# Sheet1.net
KiCad netlist of a schematic drawn in Altium Designer
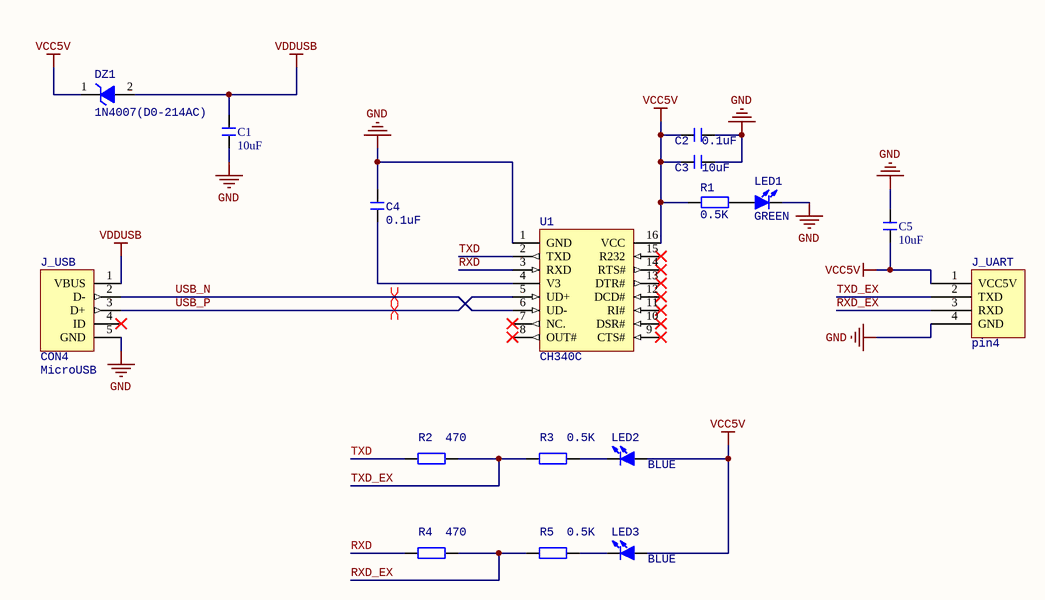
[diagram p0: Sheet1.SchDoc]

(export (version "E")
  (design (tool "Eeschema 10.0.6"))
  (components
    (comp (ref "C1")
      (value "10uF")
      (footprint "C 0603_M")
      (description "无极性贴片电容")
      (fields (field (name "版权归属") "源创客"))
      (libsource (lib "Schlib1") (part "C"))
    )
    (comp (ref "C2")
      (value "0.1uF")
      (footprint "C 0402_M")
      (description "无极性贴片电容")
      (fields (field (name "版权归属") "源创客"))
      (libsource (lib "Schlib2") (part "C"))
    )
    (comp (ref "C3")
      (value "10uF")
      (footprint "C 0603_M")
      (description "无极性贴片电容")
      (fields (field (name "版权归属") "源创客"))
      (libsource (lib "Schlib2") (part "C"))
    )
    (comp (ref "C4")
      (value "0.1uF")
      (footprint "C 0402_M")
      (description "无极性贴片电容")
      (fields (field (name "版权归属") "源创客"))
      (libsource (lib "Schlib2") (part "C"))
    )
    (comp (ref "C5")
      (value "10uF")
      (footprint "C 0603_M")
      (description "无极性贴片电容")
      (fields (field (name "版权归属") "源创客"))
      (libsource (lib "Schlib1") (part "C"))
    )
    (comp (ref "DZ1")
      (value "1N4007(D0-214AC)")
      (footprint "D SMA(DO-214AC)")
      (description "稳压二极管")
      (fields (field (name "版权归属") "源创客"))
      (libsource (lib "Schlib1") (part "DZ"))
    )
    (comp (ref "J_UART") (value "pin4") (footprint "HDR2.54-LI-4P") (libsource (lib "Schlib1") (part "pin4")))
    (comp (ref "J_USB")
      (value "CON4")
      (footprint "MicroUsb_C404969")
      (libsource (lib "Schlib1") (part "MicroUSB_5P"))
    )
    (comp (ref "LED1")
      (value "GREEN")
      (footprint "D 0402")
      (description "贴片LED")
      (fields (field (name "版权归属") "源创客"))
      (libsource (lib "Schlib2") (part "LED-SMD"))
    )
    (comp (ref "LED2")
      (value "BLUE")
      (footprint "D 0402")
      (description "贴片LED")
      (fields (field (name "版权归属") "源创客"))
      (libsource (lib "Schlib2") (part "LED-SMD"))
    )
    (comp (ref "LED3")
      (value "BLUE")
      (footprint "D 0402")
      (description "贴片LED")
      (fields (field (name "版权归属") "源创客"))
      (libsource (lib "Schlib2") (part "LED-SMD"))
    )
    (comp (ref "R1")
      (value "0.5K")
      (footprint "R 0402R")
      (description "贴片电阻")
      (libsource (lib "Schlib2") (part "R"))
    )
    (comp (ref "R2")
      (value "470")
      (footprint "R 0402R")
      (description "贴片电阻")
      (libsource (lib "Schlib2") (part "R"))
    )
    (comp (ref "R3")
      (value "0.5K")
      (footprint "R 0402R")
      (description "贴片电阻")
      (libsource (lib "Schlib2") (part "R"))
    )
    (comp (ref "R4")
      (value "470")
      (footprint "R 0402R")
      (description "贴片电阻")
      (libsource (lib "Schlib2") (part "R"))
    )
    (comp (ref "R5")
      (value "0.5K")
      (footprint "R 0402R")
      (description "贴片电阻")
      (libsource (lib "Schlib2") (part "R"))
    )
    (comp (ref "U1")
      (value "CH340C")
      (footprint "SOP-16_150mil")
      (description "CH340 是一个 USB 总线的转接芯片，实现 USB 转串口或者 USB 转打印口。")
      (libsource (lib "Schlib1") (part "CH340C"))
    )
  )
  (nets
    (net (code "1") (name "/RXD") (class "Default")
      (node (ref "R4") (pin "1") (pinfunction "1_1") (pintype "passive"))
      (node (ref "U1") (pin "3") (pinfunction "RXD_3") (pintype "input"))
    )
    (net (code "2") (name "/RXD_EX") (class "Default")
      (node (ref "J_UART") (pin "3") (pinfunction "RXD_3") (pintype "passive"))
      (node (ref "R4") (pin "2") (pinfunction "2_2") (pintype "passive"))
      (node (ref "R5") (pin "1") (pinfunction "1_1") (pintype "passive"))
    )
    (net (code "3") (name "/TXD") (class "Default")
      (node (ref "R2") (pin "1") (pinfunction "1_1") (pintype "passive"))
      (node (ref "U1") (pin "2") (pinfunction "TXD_2") (pintype "output"))
    )
    (net (code "4") (name "/TXD_EX") (class "Default")
      (node (ref "J_UART") (pin "2") (pinfunction "TXD_2") (pintype "passive"))
      (node (ref "R2") (pin "2") (pinfunction "2_2") (pintype "passive"))
      (node (ref "R3") (pin "1") (pinfunction "1_1") (pintype "passive"))
    )
    (net (code "5") (name "/USB_N") (class "Default")
      (node (ref "J_USB") (pin "2") (pinfunction "D-_2") (pintype "output"))
      (node (ref "U1") (pin "6") (pinfunction "UD-_6") (pintype "input"))
    )
    (net (code "6") (name "/USB_P") (class "Default")
      (node (ref "J_USB") (pin "3") (pinfunction "D+_3") (pintype "output"))
      (node (ref "U1") (pin "5") (pinfunction "UD+_5") (pintype "input"))
    )
    (net (code "7") (name "GND") (class "Default")
      (node (ref "C1") (pin "1") (pinfunction "1_1") (pintype "passive"))
      (node (ref "C2") (pin "2") (pinfunction "2_2") (pintype "passive"))
      (node (ref "C3") (pin "2") (pinfunction "2_2") (pintype "passive"))
      (node (ref "C4") (pin "2") (pinfunction "2_2") (pintype "passive"))
      (node (ref "C5") (pin "2") (pinfunction "2_2") (pintype "passive"))
      (node (ref "J_UART") (pin "4") (pinfunction "GND_4") (pintype "passive"))
      (node (ref "J_USB") (pin "5") (pinfunction "GND_5") (pintype "power_in"))
      (node (ref "LED1") (pin "2") (pinfunction "K_2") (pintype "passive"))
      (node (ref "U1") (pin "1") (pinfunction "GND_1") (pintype "power_in"))
    )
    (net (code "8") (name "Net-(LED1-A)") (class "Default")
      (node (ref "LED1") (pin "1") (pinfunction "A_1") (pintype "passive"))
      (node (ref "R1") (pin "2") (pinfunction "2_2") (pintype "passive"))
    )
    (net (code "9") (name "Net-(LED2-K)") (class "Default")
      (node (ref "LED2") (pin "2") (pinfunction "K_2") (pintype "passive"))
      (node (ref "R3") (pin "2") (pinfunction "2_2") (pintype "passive"))
    )
    (net (code "10") (name "Net-(LED3-K)") (class "Default")
      (node (ref "LED3") (pin "2") (pinfunction "K_2") (pintype "passive"))
      (node (ref "R5") (pin "2") (pinfunction "2_2") (pintype "passive"))
    )
    (net (code "11") (name "Net-(U1-V3)") (class "Default")
      (node (ref "C4") (pin "1") (pinfunction "1_1") (pintype "passive"))
      (node (ref "U1") (pin "4") (pinfunction "V3_4") (pintype "power_in"))
    )
    (net (code "12") (name "VCC5V") (class "Default")
      (node (ref "C2") (pin "1") (pinfunction "1_1") (pintype "passive"))
      (node (ref "C3") (pin "1") (pinfunction "1_1") (pintype "passive"))
      (node (ref "C5") (pin "1") (pinfunction "1_1") (pintype "passive"))
      (node (ref "DZ1") (pin "1") (pinfunction "K_1") (pintype "passive"))
      (node (ref "J_UART") (pin "1") (pinfunction "VCC5V_1") (pintype "passive"))
      (node (ref "LED2") (pin "1") (pinfunction "A_1") (pintype "passive"))
      (node (ref "LED3") (pin "1") (pinfunction "A_1") (pintype "passive"))
      (node (ref "R1") (pin "1") (pinfunction "1_1") (pintype "passive"))
      (node (ref "U1") (pin "16") (pinfunction "VCC_16") (pintype "power_in"))
    )
    (net (code "13") (name "VDDUSB") (class "Default")
      (node (ref "C1") (pin "2") (pinfunction "2_2") (pintype "passive"))
      (node (ref "DZ1") (pin "2") (pinfunction "A_2") (pintype "passive"))
      (node (ref "J_USB") (pin "1") (pinfunction "VBUS_1") (pintype "power_in"))
    )
    (net (code "14") (name "unconnected-(J_USB-ID-Pad4)") (class "Default")
      (node (ref "J_USB") (pin "4") (pinfunction "ID_4") (pintype "passive+no_connect"))
    )
    (net (code "15") (name "unconnected-(U1-CTS#-Pad9)") (class "Default")
      (node (ref "U1") (pin "9") (pinfunction "CTS#_9") (pintype "input+no_connect"))
    )
    (net (code "16") (name "unconnected-(U1-DCD#-Pad12)") (class "Default")
      (node (ref "U1") (pin "12") (pinfunction "DCD#_12") (pintype "input+no_connect"))
    )
    (net (code "17") (name "unconnected-(U1-DSR#-Pad10)") (class "Default")
      (node (ref "U1") (pin "10") (pinfunction "DSR#_10") (pintype "input+no_connect"))
    )
    (net (code "18") (name "unconnected-(U1-DTR#-Pad13)") (class "Default")
      (node (ref "U1") (pin "13") (pinfunction "DTR#_13") (pintype "output+no_connect"))
    )
    (net (code "19") (name "unconnected-(U1-NC.-Pad7)") (class "Default")
      (node (ref "U1") (pin "7") (pinfunction "NC._7") (pintype "output+no_connect"))
    )
    (net (code "20") (name "unconnected-(U1-OUT#-Pad8)") (class "Default")
      (node (ref "U1") (pin "8") (pinfunction "OUT#_8") (pintype "output+no_connect"))
    )
    (net (code "21") (name "unconnected-(U1-R232-Pad15)") (class "Default")
      (node (ref "U1") (pin "15") (pinfunction "R232_15") (pintype "input+no_connect"))
    )
    (net (code "22") (name "unconnected-(U1-RI#-Pad11)") (class "Default")
      (node (ref "U1") (pin "11") (pinfunction "RI#_11") (pintype "input+no_connect"))
    )
    (net (code "23") (name "unconnected-(U1-RTS#-Pad14)") (class "Default")
      (node (ref "U1") (pin "14") (pinfunction "RTS#_14") (pintype "output+no_connect"))
    )
  )
)
